# Schematic_3ph_MOSFET_Bridge.net
KiCad netlist of a schematic drawn in EAGLE
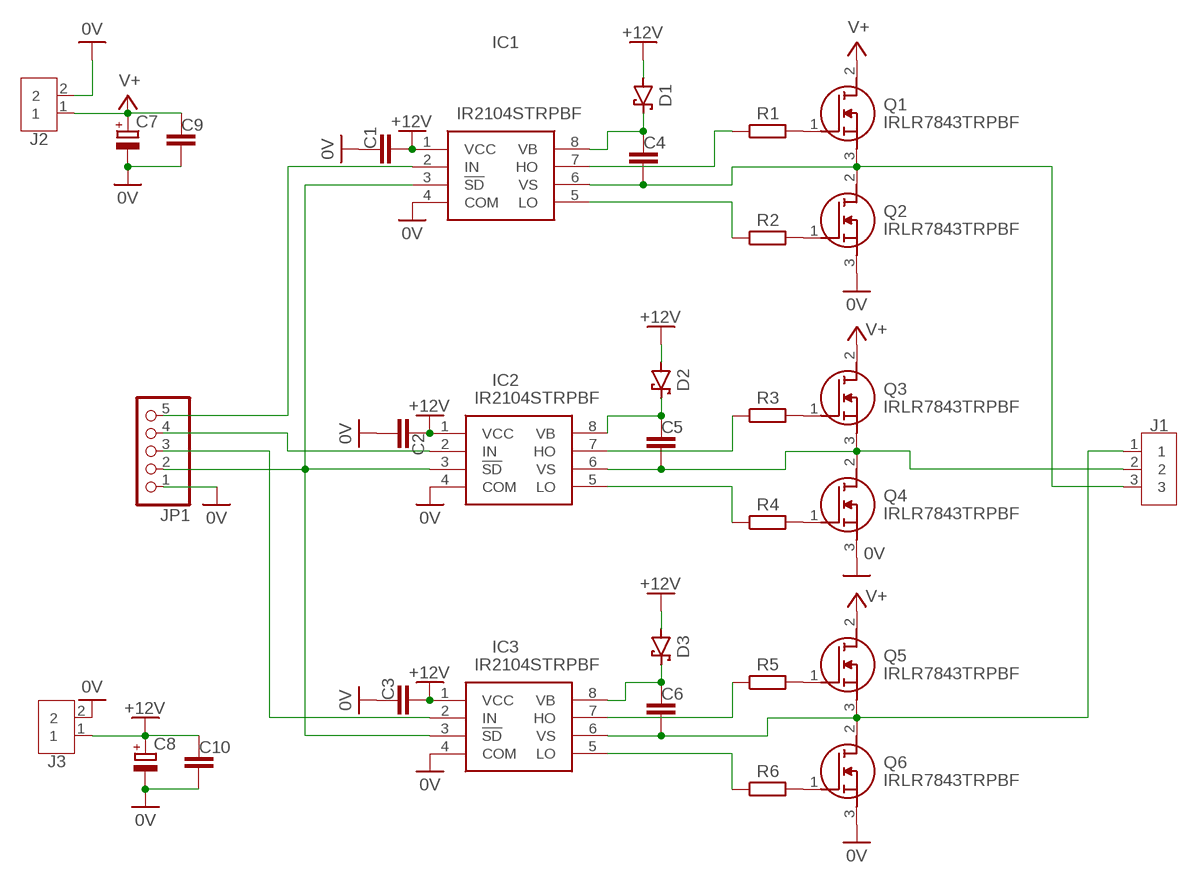
[diagram p0: schematic, sheet 1]

(export (version "E")
  (design (tool "Eeschema 10.0.6"))
  (components
    (comp (ref "C1")
      (value "CAPACITOR_CHIP-0805(2012-METRIC)")
      (footprint "eagle-import:CAPC2012X110")
      (libsource (lib "eagle-import") (part "CAPACITORCHIP-0805(2012-METRIC)_"))
    )
    (comp (ref "C2")
      (value "CAPACITOR_CHIP-0805(2012-METRIC)")
      (footprint "eagle-import:CAPC2012X110")
      (libsource (lib "eagle-import") (part "CAPACITORCHIP-0805(2012-METRIC)_"))
    )
    (comp (ref "C3")
      (value "CAPACITOR_CHIP-0805(2012-METRIC)")
      (footprint "eagle-import:CAPC2012X110")
      (libsource (lib "eagle-import") (part "CAPACITORCHIP-0805(2012-METRIC)_"))
    )
    (comp (ref "C4")
      (value "CAPACITOR_CHIP-0805(2012-METRIC)")
      (footprint "eagle-import:CAPC2012X110")
      (libsource (lib "eagle-import") (part "CAPACITORCHIP-0805(2012-METRIC)_"))
    )
    (comp (ref "C5")
      (value "CAPACITOR_CHIP-0805(2012-METRIC)")
      (footprint "eagle-import:CAPC2012X110")
      (libsource (lib "eagle-import") (part "CAPACITORCHIP-0805(2012-METRIC)_"))
    )
    (comp (ref "C6")
      (value "CAPACITOR_CHIP-0805(2012-METRIC)")
      (footprint "eagle-import:CAPC2012X110")
      (libsource (lib "eagle-import") (part "CAPACITORCHIP-0805(2012-METRIC)_"))
    )
    (comp (ref "C7")
      (value "C-POL_RADIAL-11MM-DIA")
      (footprint "eagle-import:CAPPRD508W65D1000H1100B")
      (libsource (lib "eagle-import") (part "C-POLRADIAL-11MM-DIA_"))
    )
    (comp (ref "C8")
      (value "C-POL_TANTALUM-2412(6032-METRIC)")
      (footprint "eagle-import:CAPMP6032X280N")
      (libsource (lib "eagle-import") (part "C-POLTANTALUM-2412(6032-METRIC)_"))
    )
    (comp (ref "C9")
      (value "CAPACITOR_CHIP-0805(2012-METRIC)")
      (footprint "eagle-import:CAPC2012X110")
      (libsource (lib "eagle-import") (part "CAPACITORCHIP-0805(2012-METRIC)_"))
    )
    (comp (ref "C10")
      (value "CAPACITOR_CHIP-0805(2012-METRIC)")
      (footprint "eagle-import:CAPC2012X110")
      (libsource (lib "eagle-import") (part "CAPACITORCHIP-0805(2012-METRIC)_"))
    )
    (comp (ref "D1")
      (value "MBR0520LT1G")
      (footprint "eagle-import:SODFL3718X115")
      (fields (field (name "MANUFACTURER") "ON Semiconductor"))
      (libsource (lib "eagle-import") (part "SCHOTTKY_DO-219MBR0520LT1G"))
    )
    (comp (ref "D2")
      (value "MBR0520LT1G")
      (footprint "eagle-import:SODFL3718X115")
      (fields (field (name "MANUFACTURER") "ON Semiconductor"))
      (libsource (lib "eagle-import") (part "SCHOTTKY_DO-219MBR0520LT1G"))
    )
    (comp (ref "D3")
      (value "MBR0520LT1G")
      (footprint "eagle-import:SODFL3718X115")
      (fields (field (name "MANUFACTURER") "ON Semiconductor"))
      (libsource (lib "eagle-import") (part "SCHOTTKY_DO-219MBR0520LT1G"))
    )
    (comp (ref "IC1")
      (value "IR2104STRPBF")
      (footprint "eagle-import:SOIC127P600X175-8N")
      (fields (field (name "MOUSER_PART_NUMBER") "942-IR2104STRPBF"))
      (libsource (lib "eagle-import") (part "IR2104STRPBF"))
    )
    (comp (ref "IC2")
      (value "IR2104STRPBF")
      (footprint "eagle-import:SOIC127P600X175-8N")
      (fields (field (name "MOUSER_PART_NUMBER") "942-IR2104STRPBF"))
      (libsource (lib "eagle-import") (part "IR2104STRPBF"))
    )
    (comp (ref "IC3")
      (value "IR2104STRPBF")
      (footprint "eagle-import:SOIC127P600X175-8N")
      (fields (field (name "MOUSER_PART_NUMBER") "942-IR2104STRPBF"))
      (libsource (lib "eagle-import") (part "IR2104STRPBF"))
    )
    (comp (ref "J1")
      (value "TERM-BLK-3P")
      (footprint "eagle-import:TERMBLK_508-3N")
      (fields (field (name "MANUFACTURER") "TE Connectivity") (field (name "MPN") "282837-3"))
      (libsource (lib "eagle-import") (part "2828XX-3282837-3"))
    )
    (comp (ref "J2")
      (value "TERM-BLK-2P")
      (footprint "eagle-import:TERMBLK_508-2N")
      (fields (field (name "MANUFACTURER") "TE Connectivity AMP Connectors") (field (name "MPN") "282837-2"))
      (libsource (lib "eagle-import") (part "2828XX-2282837-2"))
    )
    (comp (ref "J3")
      (value "TERM-BLK-2P")
      (footprint "eagle-import:TERMBLK_508-2N")
      (fields (field (name "MANUFACTURER") "TE Connectivity AMP Connectors") (field (name "MPN") "282837-2"))
      (libsource (lib "eagle-import") (part "2828XX-2282837-2"))
    )
    (comp (ref "JP1")
      (value "PINHD-1X5")
      (footprint "eagle-import:1X05")
      (fields (field (name "MANUFACTURER") "Generic"))
      (libsource (lib "eagle-import") (part "PINHD-1X5"))
    )
    (comp (ref "Q1")
      (value "IRLR7843TRPBF")
      (footprint "eagle-import:IRLR7843TRPBF")
      (fields (field (name "MOUSER_PART_NUMBER") "942-IRLR7843TRPBF"))
      (libsource (lib "eagle-import") (part "IRLR7843TRPBF"))
    )
    (comp (ref "Q2")
      (value "IRLR7843TRPBF")
      (footprint "eagle-import:IRLR7843TRPBF")
      (fields (field (name "MOUSER_PART_NUMBER") "942-IRLR7843TRPBF"))
      (libsource (lib "eagle-import") (part "IRLR7843TRPBF"))
    )
    (comp (ref "Q3")
      (value "IRLR7843TRPBF")
      (footprint "eagle-import:IRLR7843TRPBF")
      (fields (field (name "MOUSER_PART_NUMBER") "942-IRLR7843TRPBF"))
      (libsource (lib "eagle-import") (part "IRLR7843TRPBF"))
    )
    (comp (ref "Q4")
      (value "IRLR7843TRPBF")
      (footprint "eagle-import:IRLR7843TRPBF")
      (fields (field (name "MOUSER_PART_NUMBER") "942-IRLR7843TRPBF"))
      (libsource (lib "eagle-import") (part "IRLR7843TRPBF"))
    )
    (comp (ref "Q5")
      (value "IRLR7843TRPBF")
      (footprint "eagle-import:IRLR7843TRPBF")
      (fields (field (name "MOUSER_PART_NUMBER") "942-IRLR7843TRPBF"))
      (libsource (lib "eagle-import") (part "IRLR7843TRPBF"))
    )
    (comp (ref "Q6")
      (value "IRLR7843TRPBF")
      (footprint "eagle-import:IRLR7843TRPBF")
      (fields (field (name "MOUSER_PART_NUMBER") "942-IRLR7843TRPBF"))
      (libsource (lib "eagle-import") (part "IRLR7843TRPBF"))
    )
    (comp (ref "R1")
      (value "RESISTOR__CHIP-0805(2012-METRIC)")
      (footprint "eagle-import:RESC2012X65")
      (libsource (lib "eagle-import") (part "RESISTOR_CHIP-0805(2012-METRIC)_"))
    )
    (comp (ref "R2")
      (value "RESISTOR__CHIP-0805(2012-METRIC)")
      (footprint "eagle-import:RESC2012X65")
      (libsource (lib "eagle-import") (part "RESISTOR_CHIP-0805(2012-METRIC)_"))
    )
    (comp (ref "R3")
      (value "RESISTOR__CHIP-0805(2012-METRIC)")
      (footprint "eagle-import:RESC2012X65")
      (libsource (lib "eagle-import") (part "RESISTOR_CHIP-0805(2012-METRIC)_"))
    )
    (comp (ref "R4")
      (value "RESISTOR__CHIP-0805(2012-METRIC)")
      (footprint "eagle-import:RESC2012X65")
      (libsource (lib "eagle-import") (part "RESISTOR_CHIP-0805(2012-METRIC)_"))
    )
    (comp (ref "R5")
      (value "RESISTOR__CHIP-0805(2012-METRIC)")
      (footprint "eagle-import:RESC2012X65")
      (libsource (lib "eagle-import") (part "RESISTOR_CHIP-0805(2012-METRIC)_"))
    )
    (comp (ref "R6")
      (value "RESISTOR__CHIP-0805(2012-METRIC)")
      (footprint "eagle-import:RESC2012X65")
      (libsource (lib "eagle-import") (part "RESISTOR_CHIP-0805(2012-METRIC)_"))
    )
  )
  (nets
    (net (code "1") (name "+12V") (class "Default")
      (node (ref "C1") (pin "2") (pinfunction "2_2") (pintype "passive"))
      (node (ref "C10") (pin "1") (pinfunction "1_1") (pintype "passive"))
      (node (ref "C2") (pin "1") (pinfunction "1_1") (pintype "passive"))
      (node (ref "C3") (pin "2") (pinfunction "2_2") (pintype "passive"))
      (node (ref "C8") (pin "1") (pinfunction "+_1") (pintype "passive"))
      (node (ref "D1") (pin "2") (pinfunction "A_2") (pintype "passive"))
      (node (ref "D2") (pin "2") (pinfunction "A_2") (pintype "passive"))
      (node (ref "D3") (pin "2") (pinfunction "A_2") (pintype "passive"))
      (node (ref "IC1") (pin "1") (pinfunction "VCC_1") (pintype "bidirectional"))
      (node (ref "IC2") (pin "1") (pinfunction "VCC_1") (pintype "bidirectional"))
      (node (ref "IC3") (pin "1") (pinfunction "VCC_1") (pintype "bidirectional"))
      (node (ref "J3") (pin "1") (pinfunction "1_1") (pintype "bidirectional"))
    )
    (net (code "2") (name "0V") (class "Default")
      (node (ref "C1") (pin "1") (pinfunction "1_1") (pintype "passive"))
      (node (ref "C10") (pin "2") (pinfunction "2_2") (pintype "passive"))
      (node (ref "C2") (pin "2") (pinfunction "2_2") (pintype "passive"))
      (node (ref "C3") (pin "1") (pinfunction "1_1") (pintype "passive"))
      (node (ref "C7") (pin "2") (pinfunction "-_2") (pintype "passive"))
      (node (ref "C8") (pin "2") (pinfunction "-_2") (pintype "passive"))
      (node (ref "C9") (pin "2") (pinfunction "2_2") (pintype "passive"))
      (node (ref "IC1") (pin "4") (pinfunction "COM_4") (pintype "bidirectional"))
      (node (ref "IC2") (pin "4") (pinfunction "COM_4") (pintype "bidirectional"))
      (node (ref "IC3") (pin "4") (pinfunction "COM_4") (pintype "bidirectional"))
      (node (ref "J2") (pin "2") (pinfunction "2_2") (pintype "bidirectional"))
      (node (ref "J3") (pin "2") (pinfunction "2_2") (pintype "bidirectional"))
      (node (ref "JP1") (pin "1") (pinfunction "1_1") (pintype "passive"))
      (node (ref "Q2") (pin "3") (pinfunction "S_3") (pintype "bidirectional"))
      (node (ref "Q4") (pin "3") (pinfunction "S_3") (pintype "bidirectional"))
      (node (ref "Q6") (pin "3") (pinfunction "S_3") (pintype "bidirectional"))
    )
    (net (code "3") (name "Net-(D1-C)") (class "Default")
      (node (ref "C4") (pin "1") (pinfunction "1_1") (pintype "passive"))
      (node (ref "D1") (pin "1") (pinfunction "C_1") (pintype "passive"))
      (node (ref "IC1") (pin "8") (pinfunction "VB_8") (pintype "bidirectional"))
    )
    (net (code "4") (name "Net-(D2-C)") (class "Default")
      (node (ref "C5") (pin "1") (pinfunction "1_1") (pintype "passive"))
      (node (ref "D2") (pin "1") (pinfunction "C_1") (pintype "passive"))
      (node (ref "IC2") (pin "8") (pinfunction "VB_8") (pintype "bidirectional"))
    )
    (net (code "5") (name "Net-(D3-C)") (class "Default")
      (node (ref "C6") (pin "1") (pinfunction "1_1") (pintype "passive"))
      (node (ref "D3") (pin "1") (pinfunction "C_1") (pintype "passive"))
      (node (ref "IC3") (pin "8") (pinfunction "VB_8") (pintype "bidirectional"))
    )
    (net (code "6") (name "Net-(IC1-HO)") (class "Default")
      (node (ref "IC1") (pin "7") (pinfunction "HO_7") (pintype "bidirectional"))
      (node (ref "R1") (pin "1") (pinfunction "1_1") (pintype "passive"))
    )
    (net (code "7") (name "Net-(IC1-IN)") (class "Default")
      (node (ref "IC1") (pin "2") (pinfunction "IN_2") (pintype "bidirectional"))
      (node (ref "JP1") (pin "5") (pinfunction "5_5") (pintype "passive"))
    )
    (net (code "8") (name "Net-(IC1-LO)") (class "Default")
      (node (ref "IC1") (pin "5") (pinfunction "LO_5") (pintype "bidirectional"))
      (node (ref "R2") (pin "1") (pinfunction "1_1") (pintype "passive"))
    )
    (net (code "9") (name "Net-(IC1-VS)") (class "Default")
      (node (ref "C4") (pin "2") (pinfunction "2_2") (pintype "passive"))
      (node (ref "IC1") (pin "6") (pinfunction "VS_6") (pintype "bidirectional"))
      (node (ref "J1") (pin "3") (pinfunction "3_3") (pintype "bidirectional"))
      (node (ref "Q1") (pin "3") (pinfunction "S_3") (pintype "bidirectional"))
      (node (ref "Q2") (pin "2") (pinfunction "D_2") (pintype "bidirectional"))
    )
    (net (code "10") (name "Net-(IC1-~{SD})") (class "Default")
      (node (ref "IC1") (pin "3") (pinfunction "~{SD}_3") (pintype "bidirectional"))
      (node (ref "IC2") (pin "3") (pinfunction "~{SD}_3") (pintype "bidirectional"))
      (node (ref "IC3") (pin "3") (pinfunction "~{SD}_3") (pintype "bidirectional"))
      (node (ref "JP1") (pin "2") (pinfunction "2_2") (pintype "passive"))
    )
    (net (code "11") (name "Net-(IC2-HO)") (class "Default")
      (node (ref "IC2") (pin "7") (pinfunction "HO_7") (pintype "bidirectional"))
      (node (ref "R3") (pin "1") (pinfunction "1_1") (pintype "passive"))
    )
    (net (code "12") (name "Net-(IC2-IN)") (class "Default")
      (node (ref "IC2") (pin "2") (pinfunction "IN_2") (pintype "bidirectional"))
      (node (ref "JP1") (pin "4") (pinfunction "4_4") (pintype "passive"))
    )
    (net (code "13") (name "Net-(IC2-LO)") (class "Default")
      (node (ref "IC2") (pin "5") (pinfunction "LO_5") (pintype "bidirectional"))
      (node (ref "R4") (pin "1") (pinfunction "1_1") (pintype "passive"))
    )
    (net (code "14") (name "Net-(IC2-VS)") (class "Default")
      (node (ref "C5") (pin "2") (pinfunction "2_2") (pintype "passive"))
      (node (ref "IC2") (pin "6") (pinfunction "VS_6") (pintype "bidirectional"))
      (node (ref "J1") (pin "2") (pinfunction "2_2") (pintype "bidirectional"))
      (node (ref "Q3") (pin "3") (pinfunction "S_3") (pintype "bidirectional"))
      (node (ref "Q4") (pin "2") (pinfunction "D_2") (pintype "bidirectional"))
    )
    (net (code "15") (name "Net-(IC3-HO)") (class "Default")
      (node (ref "IC3") (pin "7") (pinfunction "HO_7") (pintype "bidirectional"))
      (node (ref "R5") (pin "1") (pinfunction "1_1") (pintype "passive"))
    )
    (net (code "16") (name "Net-(IC3-IN)") (class "Default")
      (node (ref "IC3") (pin "2") (pinfunction "IN_2") (pintype "bidirectional"))
      (node (ref "JP1") (pin "3") (pinfunction "3_3") (pintype "passive"))
    )
    (net (code "17") (name "Net-(IC3-LO)") (class "Default")
      (node (ref "IC3") (pin "5") (pinfunction "LO_5") (pintype "bidirectional"))
      (node (ref "R6") (pin "1") (pinfunction "1_1") (pintype "passive"))
    )
    (net (code "18") (name "Net-(IC3-VS)") (class "Default")
      (node (ref "C6") (pin "2") (pinfunction "2_2") (pintype "passive"))
      (node (ref "IC3") (pin "6") (pinfunction "VS_6") (pintype "bidirectional"))
      (node (ref "J1") (pin "1") (pinfunction "1_1") (pintype "bidirectional"))
      (node (ref "Q5") (pin "3") (pinfunction "S_3") (pintype "bidirectional"))
      (node (ref "Q6") (pin "2") (pinfunction "D_2") (pintype "bidirectional"))
    )
    (net (code "19") (name "Net-(Q1-G)") (class "Default")
      (node (ref "Q1") (pin "1") (pinfunction "G_1") (pintype "bidirectional"))
      (node (ref "R1") (pin "2") (pinfunction "2_2") (pintype "passive"))
    )
    (net (code "20") (name "Net-(Q2-G)") (class "Default")
      (node (ref "Q2") (pin "1") (pinfunction "G_1") (pintype "bidirectional"))
      (node (ref "R2") (pin "2") (pinfunction "2_2") (pintype "passive"))
    )
    (net (code "21") (name "Net-(Q3-G)") (class "Default")
      (node (ref "Q3") (pin "1") (pinfunction "G_1") (pintype "bidirectional"))
      (node (ref "R3") (pin "2") (pinfunction "2_2") (pintype "passive"))
    )
    (net (code "22") (name "Net-(Q4-G)") (class "Default")
      (node (ref "Q4") (pin "1") (pinfunction "G_1") (pintype "bidirectional"))
      (node (ref "R4") (pin "2") (pinfunction "2_2") (pintype "passive"))
    )
    (net (code "23") (name "Net-(Q5-G)") (class "Default")
      (node (ref "Q5") (pin "1") (pinfunction "G_1") (pintype "bidirectional"))
      (node (ref "R5") (pin "2") (pinfunction "2_2") (pintype "passive"))
    )
    (net (code "24") (name "Net-(Q6-G)") (class "Default")
      (node (ref "Q6") (pin "1") (pinfunction "G_1") (pintype "bidirectional"))
      (node (ref "R6") (pin "2") (pinfunction "2_2") (pintype "passive"))
    )
    (net (code "25") (name "V+") (class "Default")
      (node (ref "C7") (pin "1") (pinfunction "+_1") (pintype "passive"))
      (node (ref "C9") (pin "1") (pinfunction "1_1") (pintype "passive"))
      (node (ref "J2") (pin "1") (pinfunction "1_1") (pintype "bidirectional"))
      (node (ref "Q1") (pin "2") (pinfunction "D_2") (pintype "bidirectional"))
      (node (ref "Q3") (pin "2") (pinfunction "D_2") (pintype "bidirectional"))
      (node (ref "Q5") (pin "2") (pinfunction "D_2") (pintype "bidirectional"))
    )
  )
)
